# INA226.net
KiCad netlist of a schematic drawn in EAGLE
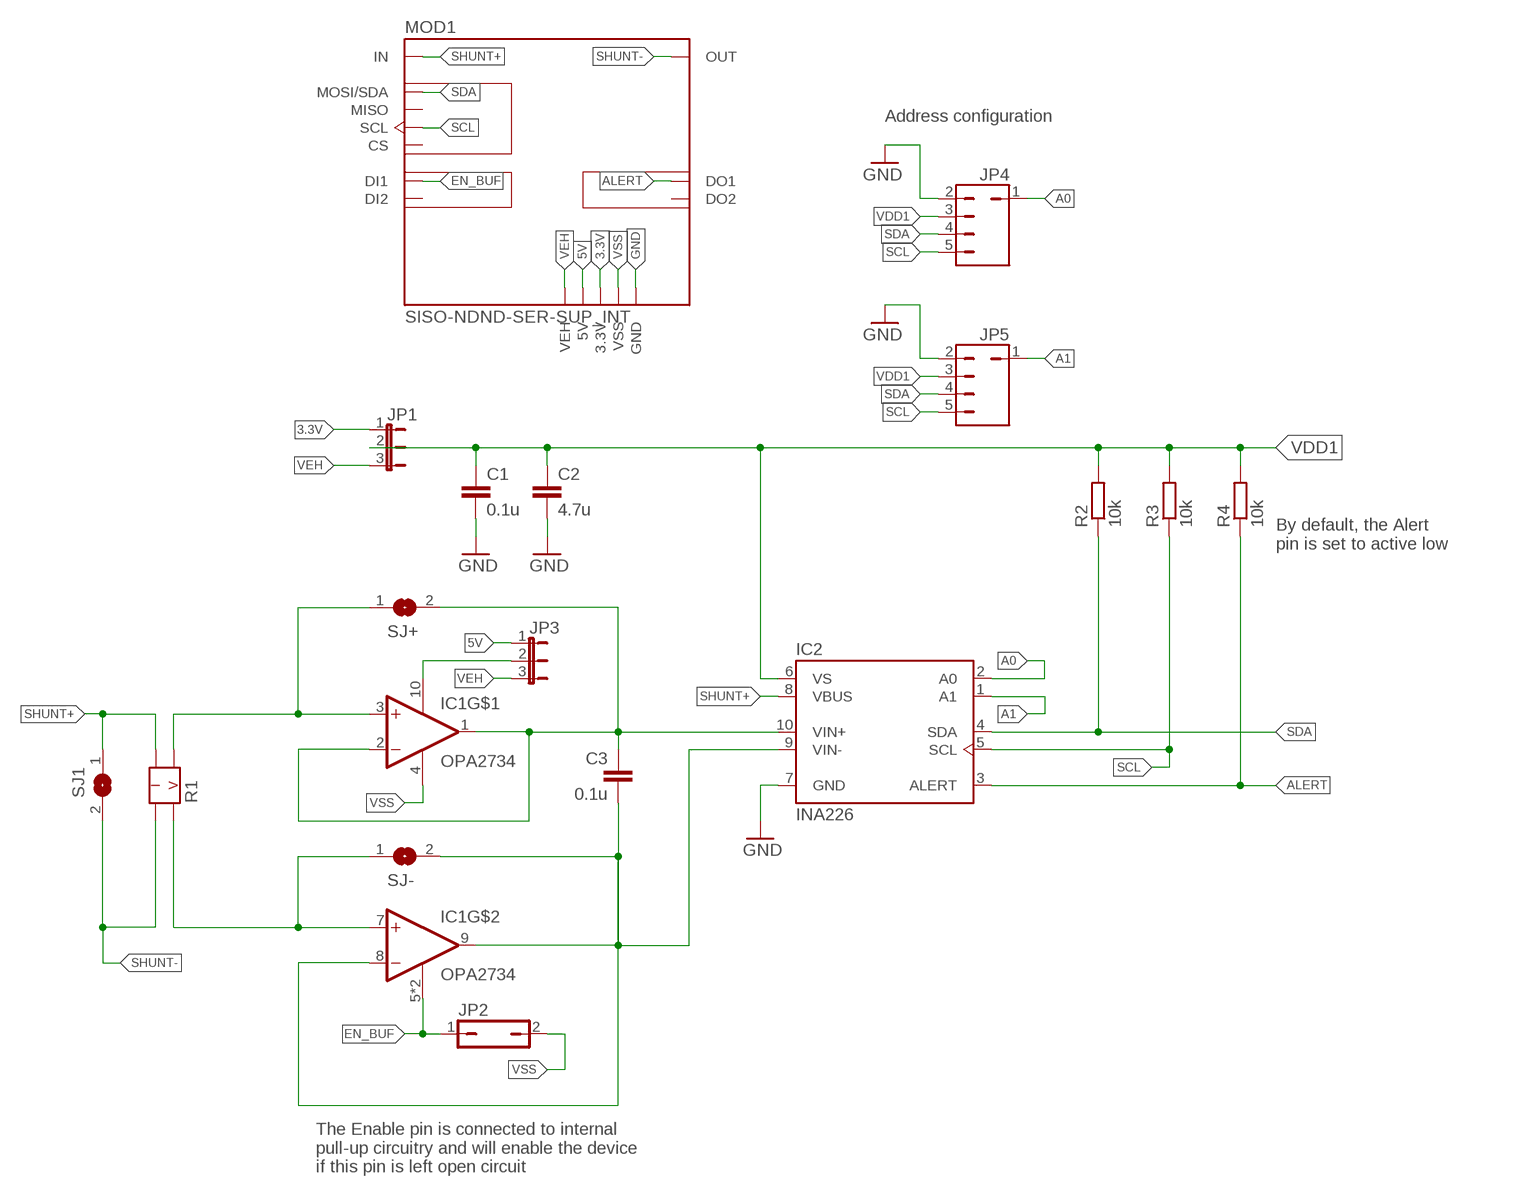
[diagram p0: schematic, sheet 1]

(export (version "E")
  (design (tool "Eeschema 10.0.6"))
  (components
    (comp (ref "C1")
      (value "0.1u")
      (footprint "eagle-import:C0805K")
      (libsource (lib "eagle-import") (part "C-EUC0805K"))
    )
    (comp (ref "C2")
      (value "4.7u")
      (footprint "eagle-import:C1206K")
      (libsource (lib "eagle-import") (part "C-EUC1206K"))
    )
    (comp (ref "C3")
      (value "0.1u")
      (footprint "eagle-import:C0805K")
      (libsource (lib "eagle-import") (part "C-EUC0805K"))
    )
    (comp (ref "IC1")
      (value "OPA2734")
      (footprint "eagle-import:MSOP10")
      (libsource (lib "eagle-import") (part "OPA2734"))
    )
    (comp (ref "IC2")
      (value "INA226")
      (footprint "eagle-import:DGS10")
      (libsource (lib "eagle-import") (part "INA226"))
    )
    (comp (ref "JP1")
      (value "JP2E")
      (footprint "eagle-import:JP2")
      (libsource (lib "eagle-import") (part "JP2E"))
    )
    (comp (ref "JP2")
      (value "JP1Q")
      (footprint "eagle-import:JP1")
      (libsource (lib "eagle-import") (part "JP1Q"))
    )
    (comp (ref "JP3")
      (value "JP2E")
      (footprint "eagle-import:JP2")
      (libsource (lib "eagle-import") (part "JP2E"))
    )
    (comp (ref "JP4")
      (value "JP3Q")
      (footprint "eagle-import:JP1-4")
      (libsource (lib "eagle-import") (part "JP3Q"))
    )
    (comp (ref "JP5")
      (value "JP3Q")
      (footprint "eagle-import:JP1-4")
      (libsource (lib "eagle-import") (part "JP3Q"))
    )
    (comp (ref "MOD1")
      (value "SISO-NDND-SER-SUP_INT")
      (footprint "eagle-import:SISO-NDND-SER-SUP")
      (libsource (lib "eagle-import") (part "SISO-NDND-SER-SUP_INT"))
    )
    (comp (ref "R1")
      (value "LVK_SERIESR1206")
      (footprint "eagle-import:LVK12")
      (libsource (lib "eagle-import") (part "LVK_SERIESR1206"))
    )
    (comp (ref "R2")
      (value "10k")
      (footprint "eagle-import:R0805")
      (libsource (lib "eagle-import") (part "R-EU_R0805"))
    )
    (comp (ref "R3")
      (value "10k")
      (footprint "eagle-import:R0805")
      (libsource (lib "eagle-import") (part "R-EU_R0805"))
    )
    (comp (ref "R4")
      (value "10k")
      (footprint "eagle-import:R0805")
      (libsource (lib "eagle-import") (part "R-EU_R0805"))
    )
    (comp (ref "SJ+")
      (value "SJ2")
      (footprint "eagle-import:SJ2")
      (libsource (lib "eagle-import") (part "SJ2"))
    )
    (comp (ref "SJ-")
      (value "SJ2")
      (footprint "eagle-import:SJ2")
      (libsource (lib "eagle-import") (part "SJ2"))
    )
    (comp (ref "SJ1") (value "SJ") (footprint "eagle-import:SJ") (libsource (lib "eagle-import") (part "SJ")))
  )
  (nets
    (net (code "1") (name "3.3V") (class "Default")
      (node (ref "JP1") (pin "1") (pinfunction "1_1") (pintype "passive"))
      (node (ref "MOD1") (pin "3.3V") (pinfunction "3.3V_3.3V") (pintype "power_in"))
    )
    (net (code "2") (name "5V") (class "Default")
      (node (ref "JP3") (pin "1") (pinfunction "1_1") (pintype "passive"))
      (node (ref "MOD1") (pin "5V") (pinfunction "5V_5V") (pintype "power_in"))
    )
    (net (code "3") (name "A0") (class "Default")
      (node (ref "IC2") (pin "2") (pinfunction "A0_2") (pintype "input"))
      (node (ref "JP4") (pin "1") (pinfunction "1_1") (pintype "passive"))
    )
    (net (code "4") (name "A1") (class "Default")
      (node (ref "IC2") (pin "1") (pinfunction "A1_1") (pintype "input"))
      (node (ref "JP5") (pin "1") (pinfunction "1_1") (pintype "passive"))
    )
    (net (code "5") (name "ALERT") (class "Default")
      (node (ref "IC2") (pin "3") (pinfunction "ALERT_3") (pintype "output"))
      (node (ref "MOD1") (pin "DO1") (pinfunction "DO1_DO1") (pintype "input"))
      (node (ref "R4") (pin "1") (pinfunction "1_1") (pintype "passive"))
    )
    (net (code "6") (name "EN_BUF") (class "Default")
      (node (ref "IC1") (pin "5") (pinfunction "EN$1_5") (pintype "input"))
      (node (ref "IC1") (pin "6") (pinfunction "EN$1_6") (pintype "input"))
      (node (ref "JP2") (pin "1") (pinfunction "1_1") (pintype "passive"))
      (node (ref "MOD1") (pin "DI1") (pinfunction "DI1_DI1") (pintype "output"))
    )
    (net (code "7") (name "GND") (class "Default")
      (node (ref "C1") (pin "2") (pinfunction "2_2") (pintype "passive"))
      (node (ref "C2") (pin "2") (pinfunction "2_2") (pintype "passive"))
      (node (ref "IC2") (pin "7") (pinfunction "GND_7") (pintype "power_in"))
      (node (ref "JP4") (pin "2") (pinfunction "2_2") (pintype "passive"))
      (node (ref "JP5") (pin "2") (pinfunction "2_2") (pintype "passive"))
      (node (ref "MOD1") (pin "GND1") (pinfunction "GND_GND1") (pintype "power_in"))
      (node (ref "MOD1") (pin "GND2") (pinfunction "GND_GND2") (pintype "power_in"))
      (node (ref "MOD1") (pin "GND3") (pinfunction "GND_GND3") (pintype "power_in"))
      (node (ref "MOD1") (pin "GND4") (pinfunction "GND_GND4") (pintype "power_in"))
    )
    (net (code "8") (name "Net-(IC1A-+IN)") (class "Default")
      (node (ref "IC1") (pin "3") (pinfunction "+IN_3") (pintype "input"))
      (node (ref "R1") (pin "V2") (pinfunction "V2_V2") (pintype "passive"))
      (node (ref "SJ+") (pin "1") (pinfunction "1_1") (pintype "passive"))
    )
    (net (code "9") (name "Net-(IC1A--IN)") (class "Default")
      (node (ref "C3") (pin "1") (pinfunction "1_1") (pintype "passive"))
      (node (ref "IC1") (pin "1") (pinfunction "OUT_1") (pintype "output"))
      (node (ref "IC1") (pin "2") (pinfunction "-IN_2") (pintype "input"))
      (node (ref "IC2") (pin "10") (pinfunction "VIN+_10") (pintype "input"))
      (node (ref "SJ+") (pin "2") (pinfunction "2_2") (pintype "passive"))
    )
    (net (code "10") (name "Net-(IC1B-+IN)") (class "Default")
      (node (ref "IC1") (pin "7") (pinfunction "+IN_7") (pintype "input"))
      (node (ref "R1") (pin "V1") (pinfunction "V1_V1") (pintype "passive"))
      (node (ref "SJ-") (pin "1") (pinfunction "1_1") (pintype "passive"))
    )
    (net (code "11") (name "Net-(IC1B--IN)") (class "Default")
      (node (ref "C3") (pin "2") (pinfunction "2_2") (pintype "passive"))
      (node (ref "IC1") (pin "8") (pinfunction "-IN_8") (pintype "input"))
      (node (ref "IC1") (pin "9") (pinfunction "OUT_9") (pintype "output"))
      (node (ref "IC2") (pin "9") (pinfunction "VIN-_9") (pintype "input"))
      (node (ref "SJ-") (pin "2") (pinfunction "2_2") (pintype "passive"))
    )
    (net (code "12") (name "Net-(IC1C-V+)") (class "Default")
      (node (ref "IC1") (pin "10") (pinfunction "V+_10") (pintype "power_in"))
      (node (ref "JP3") (pin "2") (pinfunction "2_2") (pintype "passive"))
    )
    (net (code "13") (name "SCL") (class "Default")
      (node (ref "IC2") (pin "5") (pinfunction "SCL_5") (pintype "input"))
      (node (ref "JP4") (pin "5") (pinfunction "5_5") (pintype "passive"))
      (node (ref "JP5") (pin "5") (pinfunction "5_5") (pintype "passive"))
      (node (ref "MOD1") (pin "SCL") (pinfunction "SCL_SCL") (pintype "output"))
      (node (ref "R3") (pin "1") (pinfunction "1_1") (pintype "passive"))
    )
    (net (code "14") (name "SDA") (class "Default")
      (node (ref "IC2") (pin "4") (pinfunction "SDA_4") (pintype "bidirectional"))
      (node (ref "JP4") (pin "4") (pinfunction "4_4") (pintype "passive"))
      (node (ref "JP5") (pin "4") (pinfunction "4_4") (pintype "passive"))
      (node (ref "MOD1") (pin "MOSI/SDA") (pinfunction "MOSI/SDA_MOSI/SDA") (pintype "bidirectional"))
      (node (ref "R2") (pin "1") (pinfunction "1_1") (pintype "passive"))
    )
    (net (code "15") (name "SHUNT+") (class "Default")
      (node (ref "IC2") (pin "8") (pinfunction "VBUS_8") (pintype "input"))
      (node (ref "MOD1") (pin "IN1") (pinfunction "IN_IN1") (pintype "output"))
      (node (ref "MOD1") (pin "IN2") (pinfunction "IN_IN2") (pintype "output"))
      (node (ref "MOD1") (pin "IN3") (pinfunction "IN_IN3") (pintype "output"))
      (node (ref "MOD1") (pin "IN4") (pinfunction "IN_IN4") (pintype "output"))
      (node (ref "R1") (pin "I2") (pinfunction "I2_I2") (pintype "passive"))
      (node (ref "SJ1") (pin "1") (pinfunction "1_1") (pintype "passive"))
    )
    (net (code "16") (name "SHUNT-") (class "Default")
      (node (ref "MOD1") (pin "OUT1") (pinfunction "OUT_OUT1") (pintype "input"))
      (node (ref "MOD1") (pin "OUT2") (pinfunction "OUT_OUT2") (pintype "input"))
      (node (ref "MOD1") (pin "OUT3") (pinfunction "OUT_OUT3") (pintype "input"))
      (node (ref "MOD1") (pin "OUT4") (pinfunction "OUT_OUT4") (pintype "input"))
      (node (ref "R1") (pin "I1") (pinfunction "I1_I1") (pintype "passive"))
      (node (ref "SJ1") (pin "2") (pinfunction "2_2") (pintype "passive"))
    )
    (net (code "17") (name "VDD1") (class "Default")
      (node (ref "C1") (pin "1") (pinfunction "1_1") (pintype "passive"))
      (node (ref "C2") (pin "1") (pinfunction "1_1") (pintype "passive"))
      (node (ref "IC2") (pin "6") (pinfunction "VS_6") (pintype "power_in"))
      (node (ref "JP1") (pin "2") (pinfunction "2_2") (pintype "passive"))
      (node (ref "JP4") (pin "3") (pinfunction "3_3") (pintype "passive"))
      (node (ref "JP5") (pin "3") (pinfunction "3_3") (pintype "passive"))
      (node (ref "R2") (pin "2") (pinfunction "2_2") (pintype "passive"))
      (node (ref "R3") (pin "2") (pinfunction "2_2") (pintype "passive"))
      (node (ref "R4") (pin "2") (pinfunction "2_2") (pintype "passive"))
    )
    (net (code "18") (name "VEH") (class "Default")
      (node (ref "JP1") (pin "3") (pinfunction "3_3") (pintype "passive"))
      (node (ref "JP3") (pin "3") (pinfunction "3_3") (pintype "passive"))
      (node (ref "MOD1") (pin "VEH") (pinfunction "VEH_VEH") (pintype "power_in"))
    )
    (net (code "19") (name "VSS") (class "Default")
      (node (ref "IC1") (pin "4") (pinfunction "V-_4") (pintype "power_in"))
      (node (ref "JP2") (pin "2") (pinfunction "2_2") (pintype "passive"))
      (node (ref "MOD1") (pin "VSS") (pinfunction "VSS_VSS") (pintype "power_in"))
    )
    (net (code "20") (name "unconnected-(MOD1-PadCS)") (class "Default")
      (node (ref "MOD1") (pin "CS") (pinfunction "CS_CS") (pintype "bidirectional"))
    )
    (net (code "21") (name "unconnected-(MOD1-PadDI2)") (class "Default")
      (node (ref "MOD1") (pin "DI2") (pinfunction "DI2_DI2") (pintype "output"))
    )
    (net (code "22") (name "unconnected-(MOD1-PadDO2)") (class "Default")
      (node (ref "MOD1") (pin "DO2") (pinfunction "DO2_DO2") (pintype "input"))
    )
    (net (code "23") (name "unconnected-(MOD1-PadMISO)") (class "Default")
      (node (ref "MOD1") (pin "MISO") (pinfunction "MISO_MISO") (pintype "bidirectional"))
    )
  )
)
